# DDS_channel.net
KiCad netlist of a schematic drawn in Altium Designer
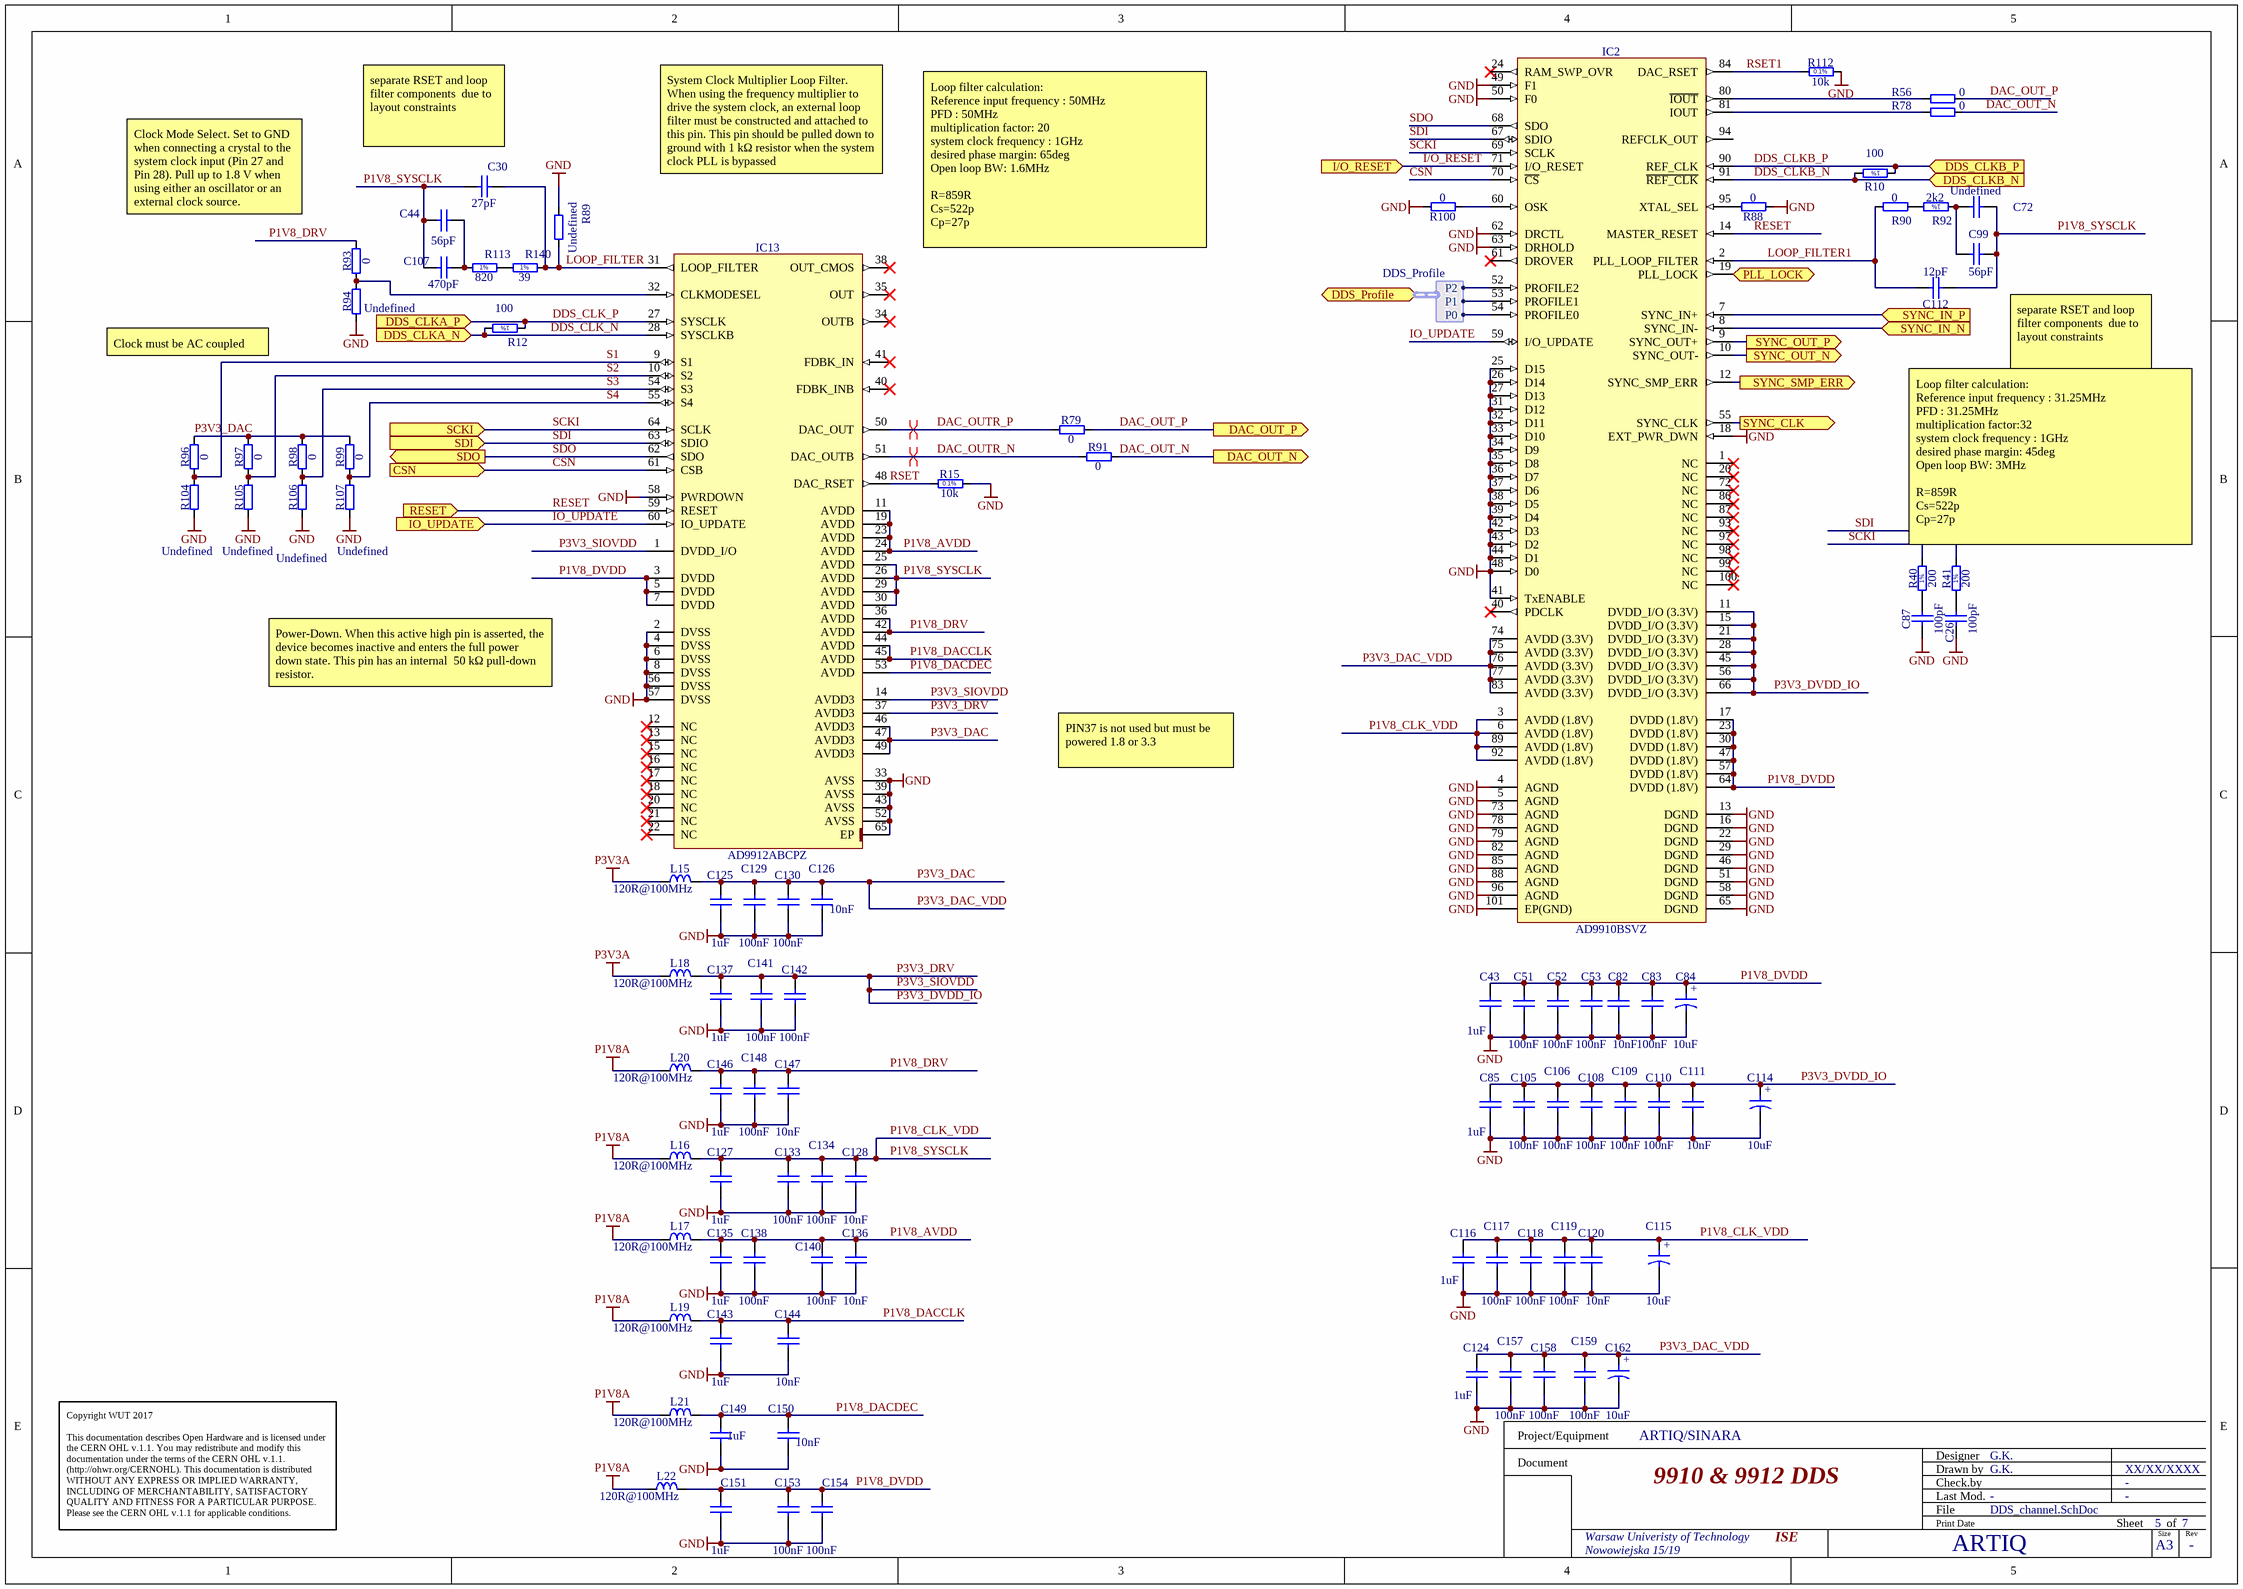
[diagram p0: DDS_channel.SchDoc]

(export (version "E")
  (design (tool "Eeschema 10.0.6"))
  (components
    (comp (ref "C26")
      (value "100pF")
      (footprint "CAPC1005X55N")
      (description "Non-polarised capacitor")
      (fields
        (field (name "PART NUMBER") "CC0402_100PF_50V_5%_C0G")
        (field (name "VOLTAGE") "50V")
        (field (name "AUTHOR") "CERN DEM JLC")
      )
      (libsource (lib "Capacitors") (part "Capacitor - non polarized"))
    )
    (comp (ref "C30")
      (value "27pF")
      (footprint "CAPC1608X87N")
      (description "Non-polarised capacitor")
      (fields
        (field (name "PART NUMBER") "CC0603_27PF_50V_5%_NP0")
        (field (name "VOLTAGE") "50V")
        (field (name "AUTHOR") "CERN DEM JLC")
      )
      (libsource (lib "Capacitors") (part "Capacitor - non polarized"))
    )
    (comp (ref "C43")
      (value "1uF")
      (footprint "CAPC1005X55N")
      (description "Non-polarised capacitor")
      (fields
        (field (name "PART NUMBER") "CC0402_1UF_16V_10%_X5R")
        (field (name "VOLTAGE") "16V")
        (field (name "AUTHOR") "CERN DEM JLC")
      )
      (libsource (lib "Capacitors") (part "Capacitor - non polarized"))
    )
    (comp (ref "C44")
      (value "56pF")
      (footprint "CAPC1608X87N")
      (description "Non-polarised capacitor")
      (fields
        (field (name "PART NUMBER") "CC0603_56PF_50V_5%_NP0")
        (field (name "VOLTAGE") "50V")
        (field (name "AUTHOR") "CERN DEM JLC")
      )
      (libsource (lib "Capacitors") (part "Capacitor - non polarized"))
    )
    (comp (ref "C51")
      (value "100nF")
      (footprint "CAPC1005X55N")
      (description "Non-polarised capacitor")
      (fields
        (field (name "PART NUMBER") "CC0402_100NF_16V_10%_X5R")
        (field (name "VOLTAGE") "16V")
        (field (name "AUTHOR") "CERN DEM JLC")
      )
      (libsource (lib "Capacitors") (part "Capacitor - non polarized"))
    )
    (comp (ref "C52")
      (value "100nF")
      (footprint "CAPC1005X55N")
      (description "Non-polarised capacitor")
      (fields
        (field (name "PART NUMBER") "CC0402_100NF_16V_10%_X5R")
        (field (name "VOLTAGE") "16V")
        (field (name "AUTHOR") "CERN DEM JLC")
      )
      (libsource (lib "Capacitors") (part "Capacitor - non polarized"))
    )
    (comp (ref "C53")
      (value "100nF")
      (footprint "CAPC1005X55N")
      (description "Non-polarised capacitor")
      (fields
        (field (name "PART NUMBER") "CC0402_100NF_16V_10%_X5R")
        (field (name "VOLTAGE") "16V")
        (field (name "AUTHOR") "CERN DEM JLC")
      )
      (libsource (lib "Capacitors") (part "Capacitor - non polarized"))
    )
    (comp (ref "C72")
      (value "Undefined")
      (footprint "CAPC1608X90N")
      (description "Non-polarised capacitor")
      (fields (field (name "PART NUMBER") "CC0603_NO-VALUE") (field (name "AUTHOR") "CERN DEM MR"))
      (libsource (lib "Capacitors") (part "Capacitor - non polarized"))
    )
    (comp (ref "C82")
      (value "10nF")
      (footprint "CAPC1005X55N")
      (description "Non-polarised capacitor")
      (fields
        (field (name "PART NUMBER") "CC0402_10NF_16V_10%_X7R")
        (field (name "VOLTAGE") "16V")
        (field (name "AUTHOR") "CERN DEM JLC")
      )
      (libsource (lib "Capacitors") (part "Capacitor - non polarized"))
    )
    (comp (ref "C83")
      (value "100nF")
      (footprint "CAPC1005X55N")
      (description "Non-polarised capacitor")
      (fields
        (field (name "PART NUMBER") "CC0402_100NF_16V_10%_X5R")
        (field (name "VOLTAGE") "16V")
        (field (name "AUTHOR") "CERN DEM JLC")
      )
      (libsource (lib "Capacitors") (part "Capacitor - non polarized"))
    )
    (comp (ref "C84")
      (value "10uF")
      (footprint "CAPMP6032X280N")
      (description "Polarised capacitor")
      (fields
        (field (name "PART NUMBER") "CTE6032-28_10UF_25V_10%_LESR0500")
        (field (name "VOLTAGE") "25V")
        (field (name "AUTHOR") "CERN DEM JLC")
      )
      (libsource (lib "Capacitors") (part "Capacitor - polarized"))
    )
    (comp (ref "C85")
      (value "1uF")
      (footprint "CAPC1005X55N")
      (description "Non-polarised capacitor")
      (fields
        (field (name "PART NUMBER") "CC0402_1UF_16V_10%_X5R")
        (field (name "VOLTAGE") "16V")
        (field (name "AUTHOR") "CERN DEM JLC")
      )
      (libsource (lib "Capacitors") (part "Capacitor - non polarized"))
    )
    (comp (ref "C87")
      (value "100pF")
      (footprint "CAPC1005X55N")
      (description "Non-polarised capacitor")
      (fields
        (field (name "PART NUMBER") "CC0402_100PF_50V_5%_C0G")
        (field (name "VOLTAGE") "50V")
        (field (name "AUTHOR") "CERN DEM JLC")
      )
      (libsource (lib "Capacitors") (part "Capacitor - non polarized"))
    )
    (comp (ref "C99")
      (value "56pF")
      (footprint "CAPC1608X87N")
      (description "Non-polarised capacitor")
      (fields
        (field (name "PART NUMBER") "CC0603_56PF_50V_5%_NP0")
        (field (name "VOLTAGE") "50V")
        (field (name "AUTHOR") "CERN DEM JLC")
      )
      (libsource (lib "Capacitors") (part "Capacitor - non polarized"))
    )
    (comp (ref "C105")
      (value "100nF")
      (footprint "CAPC1005X55N")
      (description "Non-polarised capacitor")
      (fields
        (field (name "PART NUMBER") "CC0402_100NF_16V_10%_X5R")
        (field (name "VOLTAGE") "16V")
        (field (name "AUTHOR") "CERN DEM JLC")
      )
      (libsource (lib "Capacitors") (part "Capacitor - non polarized"))
    )
    (comp (ref "C106")
      (value "100nF")
      (footprint "CAPC1005X55N")
      (description "Non-polarised capacitor")
      (fields
        (field (name "PART NUMBER") "CC0402_100NF_16V_10%_X5R")
        (field (name "VOLTAGE") "16V")
        (field (name "AUTHOR") "CERN DEM JLC")
      )
      (libsource (lib "Capacitors") (part "Capacitor - non polarized"))
    )
    (comp (ref "C107")
      (value "470pF")
      (footprint "CAPC1608X87N")
      (description "Non-polarised capacitor")
      (fields
        (field (name "PART NUMBER") "CC0603_470PF_50V_5%_NP0")
        (field (name "VOLTAGE") "50V")
        (field (name "AUTHOR") "CERN DEM JLC")
      )
      (libsource (lib "Capacitors") (part "Capacitor - non polarized"))
    )
    (comp (ref "C108")
      (value "100nF")
      (footprint "CAPC1005X55N")
      (description "Non-polarised capacitor")
      (fields
        (field (name "PART NUMBER") "CC0402_100NF_16V_10%_X5R")
        (field (name "VOLTAGE") "16V")
        (field (name "AUTHOR") "CERN DEM JLC")
      )
      (libsource (lib "Capacitors") (part "Capacitor - non polarized"))
    )
    (comp (ref "C109")
      (value "100nF")
      (footprint "CAPC1005X55N")
      (description "Non-polarised capacitor")
      (fields
        (field (name "PART NUMBER") "CC0402_100NF_16V_10%_X5R")
        (field (name "VOLTAGE") "16V")
        (field (name "AUTHOR") "CERN DEM JLC")
      )
      (libsource (lib "Capacitors") (part "Capacitor - non polarized"))
    )
    (comp (ref "C110")
      (value "100nF")
      (footprint "CAPC1005X55N")
      (description "Non-polarised capacitor")
      (fields
        (field (name "PART NUMBER") "CC0402_100NF_16V_10%_X5R")
        (field (name "VOLTAGE") "16V")
        (field (name "AUTHOR") "CERN DEM JLC")
      )
      (libsource (lib "Capacitors") (part "Capacitor - non polarized"))
    )
    (comp (ref "C111")
      (value "10nF")
      (footprint "CAPC1005X55N")
      (description "Non-polarised capacitor")
      (fields
        (field (name "PART NUMBER") "CC0402_10NF_16V_10%_X7R")
        (field (name "VOLTAGE") "16V")
        (field (name "AUTHOR") "CERN DEM JLC")
      )
      (libsource (lib "Capacitors") (part "Capacitor - non polarized"))
    )
    (comp (ref "C112")
      (value "12pF")
      (footprint "CAPC1608X87N")
      (description "Non-polarised capacitor")
      (fields
        (field (name "PART NUMBER") "CC0603_12PF_50V_5%_NP0")
        (field (name "VOLTAGE") "50V")
        (field (name "AUTHOR") "CERN DEM JLC")
      )
      (libsource (lib "Capacitors") (part "Capacitor - non polarized"))
    )
    (comp (ref "C114")
      (value "10uF")
      (footprint "CAPMP6032X280N")
      (description "Polarised capacitor")
      (fields
        (field (name "PART NUMBER") "CTE6032-28_10UF_25V_10%_LESR0500")
        (field (name "VOLTAGE") "25V")
        (field (name "AUTHOR") "CERN DEM JLC")
      )
      (libsource (lib "Capacitors") (part "Capacitor - polarized"))
    )
    (comp (ref "C115")
      (value "10uF")
      (footprint "CAPMP6032X280N")
      (description "Polarised capacitor")
      (fields
        (field (name "PART NUMBER") "CTE6032-28_10UF_25V_10%_LESR0500")
        (field (name "VOLTAGE") "25V")
        (field (name "AUTHOR") "CERN DEM JLC")
      )
      (libsource (lib "Capacitors") (part "Capacitor - polarized"))
    )
    (comp (ref "C116")
      (value "1uF")
      (footprint "CAPC1005X55N")
      (description "Non-polarised capacitor")
      (fields
        (field (name "PART NUMBER") "CC0402_1UF_16V_10%_X5R")
        (field (name "VOLTAGE") "16V")
        (field (name "AUTHOR") "CERN DEM JLC")
      )
      (libsource (lib "Capacitors") (part "Capacitor - non polarized"))
    )
    (comp (ref "C117")
      (value "100nF")
      (footprint "CAPC1005X55N")
      (description "Non-polarised capacitor")
      (fields
        (field (name "PART NUMBER") "CC0402_100NF_16V_10%_X5R")
        (field (name "VOLTAGE") "16V")
        (field (name "AUTHOR") "CERN DEM JLC")
      )
      (libsource (lib "Capacitors") (part "Capacitor - non polarized"))
    )
    (comp (ref "C118")
      (value "100nF")
      (footprint "CAPC1005X55N")
      (description "Non-polarised capacitor")
      (fields
        (field (name "PART NUMBER") "CC0402_100NF_16V_10%_X5R")
        (field (name "VOLTAGE") "16V")
        (field (name "AUTHOR") "CERN DEM JLC")
      )
      (libsource (lib "Capacitors") (part "Capacitor - non polarized"))
    )
    (comp (ref "C119")
      (value "100nF")
      (footprint "CAPC1005X55N")
      (description "Non-polarised capacitor")
      (fields
        (field (name "PART NUMBER") "CC0402_100NF_16V_10%_X5R")
        (field (name "VOLTAGE") "16V")
        (field (name "AUTHOR") "CERN DEM JLC")
      )
      (libsource (lib "Capacitors") (part "Capacitor - non polarized"))
    )
    (comp (ref "C120")
      (value "10nF")
      (footprint "CAPC1005X55N")
      (description "Non-polarised capacitor")
      (fields
        (field (name "PART NUMBER") "CC0402_10NF_16V_10%_X7R")
        (field (name "VOLTAGE") "16V")
        (field (name "AUTHOR") "CERN DEM JLC")
      )
      (libsource (lib "Capacitors") (part "Capacitor - non polarized"))
    )
    (comp (ref "C124")
      (value "1uF")
      (footprint "CAPC1005X55N")
      (description "Non-polarised capacitor")
      (fields
        (field (name "PART NUMBER") "CC0402_1UF_16V_10%_X5R")
        (field (name "VOLTAGE") "16V")
        (field (name "AUTHOR") "CERN DEM JLC")
      )
      (libsource (lib "Capacitors") (part "Capacitor - non polarized"))
    )
    (comp (ref "C125")
      (value "1uF")
      (footprint "CAPC1005X55N")
      (description "Non-polarised capacitor")
      (fields
        (field (name "PART NUMBER") "CC0402_1UF_16V_10%_X5R")
        (field (name "VOLTAGE") "16V")
        (field (name "AUTHOR") "CERN DEM JLC")
      )
      (libsource (lib "Capacitors") (part "Capacitor - non polarized"))
    )
    (comp (ref "C126")
      (value "10nF")
      (footprint "CAPC1005X55N")
      (description "Non-polarised capacitor")
      (fields
        (field (name "PART NUMBER") "CC0402_10NF_16V_10%_X7R")
        (field (name "VOLTAGE") "16V")
        (field (name "AUTHOR") "CERN DEM JLC")
      )
      (libsource (lib "Capacitors") (part "Capacitor - non polarized"))
    )
    (comp (ref "C127")
      (value "1uF")
      (footprint "CAPC1005X55N")
      (description "Non-polarised capacitor")
      (fields
        (field (name "PART NUMBER") "CC0402_1UF_16V_10%_X5R")
        (field (name "VOLTAGE") "16V")
        (field (name "AUTHOR") "CERN DEM JLC")
      )
      (libsource (lib "Capacitors") (part "Capacitor - non polarized"))
    )
    (comp (ref "C128")
      (value "10nF")
      (footprint "CAPC1005X55N")
      (description "Non-polarised capacitor")
      (fields
        (field (name "PART NUMBER") "CC0402_10NF_16V_10%_X7R")
        (field (name "VOLTAGE") "16V")
        (field (name "AUTHOR") "CERN DEM JLC")
      )
      (libsource (lib "Capacitors") (part "Capacitor - non polarized"))
    )
    (comp (ref "C129")
      (value "100nF")
      (footprint "CAPC1005X55N")
      (description "Non-polarised capacitor")
      (fields
        (field (name "PART NUMBER") "CC0402_100NF_16V_10%_X5R")
        (field (name "VOLTAGE") "16V")
        (field (name "AUTHOR") "CERN DEM JLC")
      )
      (libsource (lib "Capacitors") (part "Capacitor - non polarized"))
    )
    (comp (ref "C130")
      (value "100nF")
      (footprint "CAPC1005X55N")
      (description "Non-polarised capacitor")
      (fields
        (field (name "PART NUMBER") "CC0402_100NF_16V_10%_X5R")
        (field (name "VOLTAGE") "16V")
        (field (name "AUTHOR") "CERN DEM JLC")
      )
      (libsource (lib "Capacitors") (part "Capacitor - non polarized"))
    )
    (comp (ref "C133")
      (value "100nF")
      (footprint "CAPC1005X55N")
      (description "Non-polarised capacitor")
      (fields
        (field (name "PART NUMBER") "CC0402_100NF_16V_10%_X5R")
        (field (name "VOLTAGE") "16V")
        (field (name "AUTHOR") "CERN DEM JLC")
      )
      (libsource (lib "Capacitors") (part "Capacitor - non polarized"))
    )
    (comp (ref "C134")
      (value "100nF")
      (footprint "CAPC1005X55N")
      (description "Non-polarised capacitor")
      (fields
        (field (name "PART NUMBER") "CC0402_100NF_16V_10%_X5R")
        (field (name "VOLTAGE") "16V")
        (field (name "AUTHOR") "CERN DEM JLC")
      )
      (libsource (lib "Capacitors") (part "Capacitor - non polarized"))
    )
    (comp (ref "C135")
      (value "1uF")
      (footprint "CAPC1005X55N")
      (description "Non-polarised capacitor")
      (fields
        (field (name "PART NUMBER") "CC0402_1UF_16V_10%_X5R")
        (field (name "VOLTAGE") "16V")
        (field (name "AUTHOR") "CERN DEM JLC")
      )
      (libsource (lib "Capacitors") (part "Capacitor - non polarized"))
    )
    (comp (ref "C136")
      (value "10nF")
      (footprint "CAPC1005X55N")
      (description "Non-polarised capacitor")
      (fields
        (field (name "PART NUMBER") "CC0402_10NF_16V_10%_X7R")
        (field (name "VOLTAGE") "16V")
        (field (name "AUTHOR") "CERN DEM JLC")
      )
      (libsource (lib "Capacitors") (part "Capacitor - non polarized"))
    )
    (comp (ref "C137")
      (value "1uF")
      (footprint "CAPC1005X55N")
      (description "Non-polarised capacitor")
      (fields
        (field (name "PART NUMBER") "CC0402_1UF_16V_10%_X5R")
        (field (name "VOLTAGE") "16V")
        (field (name "AUTHOR") "CERN DEM JLC")
      )
      (libsource (lib "Capacitors") (part "Capacitor - non polarized"))
    )
    (comp (ref "C138")
      (value "100nF")
      (footprint "CAPC1005X55N")
      (description "Non-polarised capacitor")
      (fields
        (field (name "PART NUMBER") "CC0402_100NF_16V_10%_X5R")
        (field (name "VOLTAGE") "16V")
        (field (name "AUTHOR") "CERN DEM JLC")
      )
      (libsource (lib "Capacitors") (part "Capacitor - non polarized"))
    )
    (comp (ref "C140")
      (value "100nF")
      (footprint "CAPC1005X55N")
      (description "Non-polarised capacitor")
      (fields
        (field (name "PART NUMBER") "CC0402_100NF_16V_10%_X5R")
        (field (name "VOLTAGE") "16V")
        (field (name "AUTHOR") "CERN DEM JLC")
      )
      (libsource (lib "Capacitors") (part "Capacitor - non polarized"))
    )
    (comp (ref "C141")
      (value "100nF")
      (footprint "CAPC1005X55N")
      (description "Non-polarised capacitor")
      (fields
        (field (name "PART NUMBER") "CC0402_100NF_16V_10%_X5R")
        (field (name "VOLTAGE") "16V")
        (field (name "AUTHOR") "CERN DEM JLC")
      )
      (libsource (lib "Capacitors") (part "Capacitor - non polarized"))
    )
    (comp (ref "C142")
      (value "100nF")
      (footprint "CAPC1005X55N")
      (description "Non-polarised capacitor")
      (fields
        (field (name "PART NUMBER") "CC0402_100NF_16V_10%_X5R")
        (field (name "VOLTAGE") "16V")
        (field (name "AUTHOR") "CERN DEM JLC")
      )
      (libsource (lib "Capacitors") (part "Capacitor - non polarized"))
    )
    (comp (ref "C143")
      (value "1uF")
      (footprint "CAPC1005X55N")
      (description "Non-polarised capacitor")
      (fields
        (field (name "PART NUMBER") "CC0402_1UF_16V_10%_X5R")
        (field (name "VOLTAGE") "16V")
        (field (name "AUTHOR") "CERN DEM JLC")
      )
      (libsource (lib "Capacitors") (part "Capacitor - non polarized"))
    )
    (comp (ref "C144")
      (value "10nF")
      (footprint "CAPC1005X55N")
      (description "Non-polarised capacitor")
      (fields
        (field (name "PART NUMBER") "CC0402_10NF_16V_10%_X7R")
        (field (name "VOLTAGE") "16V")
        (field (name "AUTHOR") "CERN DEM JLC")
      )
      (libsource (lib "Capacitors") (part "Capacitor - non polarized"))
    )
    (comp (ref "C146")
      (value "1uF")
      (footprint "CAPC1005X55N")
      (description "Non-polarised capacitor")
      (fields
        (field (name "PART NUMBER") "CC0402_1UF_16V_10%_X5R")
        (field (name "VOLTAGE") "16V")
        (field (name "AUTHOR") "CERN DEM JLC")
      )
      (libsource (lib "Capacitors") (part "Capacitor - non polarized"))
    )
    (comp (ref "C147")
      (value "10nF")
      (footprint "CAPC1005X55N")
      (description "Non-polarised capacitor")
      (fields
        (field (name "PART NUMBER") "CC0402_10NF_16V_10%_X7R")
        (field (name "VOLTAGE") "16V")
        (field (name "AUTHOR") "CERN DEM JLC")
      )
      (libsource (lib "Capacitors") (part "Capacitor - non polarized"))
    )
    (comp (ref "C148")
      (value "100nF")
      (footprint "CAPC1005X55N")
      (description "Non-polarised capacitor")
      (fields
        (field (name "PART NUMBER") "CC0402_100NF_16V_10%_X5R")
        (field (name "VOLTAGE") "16V")
        (field (name "AUTHOR") "CERN DEM JLC")
      )
      (libsource (lib "Capacitors") (part "Capacitor - non polarized"))
    )
    (comp (ref "C149")
      (value "1uF")
      (footprint "CAPC1005X55N")
      (description "Non-polarised capacitor")
      (fields
        (field (name "PART NUMBER") "CC0402_1UF_16V_10%_X5R")
        (field (name "VOLTAGE") "16V")
        (field (name "AUTHOR") "CERN DEM JLC")
      )
      (libsource (lib "Capacitors") (part "Capacitor - non polarized"))
    )
    (comp (ref "C150")
      (value "10nF")
      (footprint "CAPC1005X55N")
      (description "Non-polarised capacitor")
      (fields
        (field (name "PART NUMBER") "CC0402_10NF_16V_10%_X7R")
        (field (name "VOLTAGE") "16V")
        (field (name "AUTHOR") "CERN DEM JLC")
      )
      (libsource (lib "Capacitors") (part "Capacitor - non polarized"))
    )
    (comp (ref "C151")
      (value "1uF")
      (footprint "CAPC1005X55N")
      (description "Non-polarised capacitor")
      (fields
        (field (name "PART NUMBER") "CC0402_1UF_16V_10%_X5R")
        (field (name "VOLTAGE") "16V")
        (field (name "AUTHOR") "CERN DEM JLC")
      )
      (libsource (lib "Capacitors") (part "Capacitor - non polarized"))
    )
    (comp (ref "C153")
      (value "100nF")
      (footprint "CAPC1005X55N")
      (description "Non-polarised capacitor")
      (fields
        (field (name "PART NUMBER") "CC0402_100NF_16V_10%_X5R")
        (field (name "VOLTAGE") "16V")
        (field (name "AUTHOR") "CERN DEM JLC")
      )
      (libsource (lib "Capacitors") (part "Capacitor - non polarized"))
    )
    (comp (ref "C154")
      (value "100nF")
      (footprint "CAPC1005X55N")
      (description "Non-polarised capacitor")
      (fields
        (field (name "PART NUMBER") "CC0402_100NF_16V_10%_X5R")
        (field (name "VOLTAGE") "16V")
        (field (name "AUTHOR") "CERN DEM JLC")
      )
      (libsource (lib "Capacitors") (part "Capacitor - non polarized"))
    )
    (comp (ref "C157")
      (value "100nF")
      (footprint "CAPC1005X55N")
      (description "Non-polarised capacitor")
      (fields
        (field (name "PART NUMBER") "CC0402_100NF_16V_10%_X5R")
        (field (name "VOLTAGE") "16V")
        (field (name "AUTHOR") "CERN DEM JLC")
      )
      (libsource (lib "Capacitors") (part "Capacitor - non polarized"))
    )
    (comp (ref "C158")
      (value "100nF")
      (footprint "CAPC1005X55N")
      (description "Non-polarised capacitor")
      (fields
        (field (name "PART NUMBER") "CC0402_100NF_16V_10%_X5R")
        (field (name "VOLTAGE") "16V")
        (field (name "AUTHOR") "CERN DEM JLC")
      )
      (libsource (lib "Capacitors") (part "Capacitor - non polarized"))
    )
    (comp (ref "C159")
      (value "100nF")
      (footprint "CAPC1005X55N")
      (description "Non-polarised capacitor")
      (fields
        (field (name "PART NUMBER") "CC0402_100NF_16V_10%_X5R")
        (field (name "VOLTAGE") "16V")
        (field (name "AUTHOR") "CERN DEM JLC")
      )
      (libsource (lib "Capacitors") (part "Capacitor - non polarized"))
    )
    (comp (ref "C162")
      (value "10uF")
      (footprint "CAPMP6032X280N")
      (description "Polarised capacitor")
      (fields
        (field (name "PART NUMBER") "CTE6032-28_10UF_25V_10%_LESR0500")
        (field (name "VOLTAGE") "25V")
        (field (name "AUTHOR") "CERN DEM JLC")
      )
      (libsource (lib "Capacitors") (part "Capacitor - polarized"))
    )
    (comp (ref "IC2")
      (value "AD9910BSVZ")
      (footprint "QFP50P1600X1600X120-101N-S500")
      (description "1 GSPS, 14-Bit, 3.3 V CMOS Direct Digital Synthesizer")
      (fields (field (name "MANUFACTURER") "ANALOG DEVICES") (field (name "AUTHOR") "CERN DEM JLC"))
      (libsource (lib "ICs And Semiconductors") (part "AD9910"))
    )
    (comp (ref "IC13")
      (value "AD9912ABCPZ")
      (footprint "QFN50P900X900X100-65N-S536")
      (description "1 GSPS Direct Digital Synthetizer with 14-Bit DAC")
      (fields (field (name "MANUFACTURER") "ANALOG DEVICES") (field (name "AUTHOR") "CERN DEM JLC"))
      (libsource (lib "ICs And Semiconductors") (part "AD9912"))
    )
    (comp (ref "L15")
      (value "120R@100MHz")
      (footprint "INDC1608X95N")
      (description "Inductor")
      (fields
        (field (name "PART NUMBER") "IND0603_MURATA_BLM18PG121SN1D")
        (field (name "POWER") "2A")
        (field (name "AUTHOR") "CERN DEM BC")
      )
      (libsource (lib "Inductors & Transformers") (part "Inductor"))
    )
    (comp (ref "L16")
      (value "120R@100MHz")
      (footprint "INDC1608X95N")
      (description "Inductor")
      (fields
        (field (name "PART NUMBER") "IND0603_MURATA_BLM18PG121SN1D")
        (field (name "POWER") "2A")
        (field (name "AUTHOR") "CERN DEM BC")
      )
      (libsource (lib "Inductors & Transformers") (part "Inductor"))
    )
    (comp (ref "L17")
      (value "120R@100MHz")
      (footprint "INDC1608X95N")
      (description "Inductor")
      (fields
        (field (name "PART NUMBER") "IND0603_MURATA_BLM18PG121SN1D")
        (field (name "POWER") "2A")
        (field (name "AUTHOR") "CERN DEM BC")
      )
      (libsource (lib "Inductors & Transformers") (part "Inductor"))
    )
    (comp (ref "L18")
      (value "120R@100MHz")
      (footprint "INDC1608X95N")
      (description "Inductor")
      (fields
        (field (name "PART NUMBER") "IND0603_MURATA_BLM18PG121SN1D")
        (field (name "POWER") "2A")
        (field (name "AUTHOR") "CERN DEM BC")
      )
      (libsource (lib "Inductors & Transformers") (part "Inductor"))
    )
    (comp (ref "L19")
      (value "120R@100MHz")
      (footprint "INDC1608X95N")
      (description "Inductor")
      (fields
        (field (name "PART NUMBER") "IND0603_MURATA_BLM18PG121SN1D")
        (field (name "POWER") "2A")
        (field (name "AUTHOR") "CERN DEM BC")
      )
      (libsource (lib "Inductors & Transformers") (part "Inductor"))
    )
    (comp (ref "L20")
      (value "120R@100MHz")
      (footprint "INDC1608X95N")
      (description "Inductor")
      (fields
        (field (name "PART NUMBER") "IND0603_MURATA_BLM18PG121SN1D")
        (field (name "POWER") "2A")
        (field (name "AUTHOR") "CERN DEM BC")
      )
      (libsource (lib "Inductors & Transformers") (part "Inductor"))
    )
    (comp (ref "L21")
      (value "120R@100MHz")
      (footprint "INDC1608X95N")
      (description "Inductor")
      (fields
        (field (name "PART NUMBER") "IND0603_MURATA_BLM18PG121SN1D")
        (field (name "POWER") "2A")
        (field (name "AUTHOR") "CERN DEM BC")
      )
      (libsource (lib "Inductors & Transformers") (part "Inductor"))
    )
    (comp (ref "L22")
      (value "120R@100MHz")
      (footprint "INDC1608X95N")
      (description "Inductor")
      (fields
        (field (name "PART NUMBER") "IND0603_MURATA_BLM18PG121SN1D")
        (field (name "POWER") "2A")
        (field (name "AUTHOR") "CERN DEM BC")
      )
      (libsource (lib "Inductors & Transformers") (part "Inductor"))
    )
    (comp (ref "R10")
      (value "100")
      (footprint "RESC1005X40N")
      (description "Resistor - 1%")
      (fields
        (field (name "PART NUMBER") "R0402_100R_1%_0.0625W_100PPM")
        (field (name "POWER") "0.0625W")
        (field (name "AUTHOR") "CERN DEM JLC")
      )
      (libsource (lib "Resistors") (part "Resistor - 1%"))
    )
    (comp (ref "R12")
      (value "100")
      (footprint "RESC1005X40N")
      (description "Resistor - 1%")
      (fields
        (field (name "PART NUMBER") "R0402_100R_1%_0.0625W_100PPM")
        (field (name "POWER") "0.0625W")
        (field (name "AUTHOR") "CERN DEM JLC")
      )
      (libsource (lib "Resistors") (part "Resistor - 1%"))
    )
    (comp (ref "R15")
      (value "10k")
      (footprint "RESC1005X35N")
      (description "Resistor - 0.1%")
      (fields
        (field (name "PART NUMBER") "R0402_10K_0.1%_0.063W_25PPM")
        (field (name "POWER") "0.063W")
        (field (name "AUTHOR") "CERN DEM JMW")
      )
      (libsource (lib "Resistors") (part "Resistor - 0.1%"))
    )
    (comp (ref "R40")
      (value "200")
      (footprint "RESC1005X40N")
      (description "Resistor - 1%")
      (fields
        (field (name "PART NUMBER") "R0402_200R_1%_0.0625W_100PPM")
        (field (name "POWER") "0.0625W")
        (field (name "AUTHOR") "CERN DEM JLC")
      )
      (libsource (lib "Resistors") (part "Resistor - 1%"))
    )
    (comp (ref "R41")
      (value "200")
      (footprint "RESC1005X40N")
      (description "Resistor - 1%")
      (fields
        (field (name "PART NUMBER") "R0402_200R_1%_0.0625W_100PPM")
        (field (name "POWER") "0.0625W")
        (field (name "AUTHOR") "CERN DEM JLC")
      )
      (libsource (lib "Resistors") (part "Resistor - 1%"))
    )
    (comp (ref "R56")
      (value "0")
      (footprint "RESC1005X40N")
      (description "Resistor")
      (fields
        (field (name "PART NUMBER") "R0402_0R_JUMPER")
        (field (name "MANUFACTURER") "GENERIC")
        (field (name "AUTHOR") "CERN DEM JLC")
      )
      (libsource (lib "Resistors") (part "Resistor"))
    )
    (comp (ref "R78")
      (value "0")
      (footprint "RESC1005X40N")
      (description "Resistor")
      (fields
        (field (name "PART NUMBER") "R0402_0R_JUMPER")
        (field (name "MANUFACTURER") "GENERIC")
        (field (name "AUTHOR") "CERN DEM JLC")
      )
      (libsource (lib "Resistors") (part "Resistor"))
    )
    (comp (ref "R79")
      (value "0")
      (footprint "RESC1005X40N")
      (description "Resistor")
      (fields
        (field (name "PART NUMBER") "R0402_0R_JUMPER")
        (field (name "MANUFACTURER") "GENERIC")
        (field (name "AUTHOR") "CERN DEM JLC")
      )
      (libsource (lib "Resistors") (part "Resistor"))
    )
    (comp (ref "R88")
      (value "0")
      (footprint "RESC1005X40N")
      (description "Resistor")
      (fields
        (field (name "PART NUMBER") "R0402_0R_JUMPER")
        (field (name "MANUFACTURER") "GENERIC")
        (field (name "AUTHOR") "CERN DEM JLC")
      )
      (libsource (lib "Resistors") (part "Resistor"))
    )
    (comp (ref "R89")
      (value "Undefined")
      (footprint "RESC1005X40N")
      (description "Resistor")
      (fields (field (name "PART NUMBER") "R0402_NO-VALUE") (field (name "AUTHOR") "CERN DEM JLC"))
      (libsource (lib "Resistors") (part "Resistor"))
    )
    (comp (ref "R90")
      (value "0")
      (footprint "RESC1608X55N")
      (description "Resistor")
      (fields
        (field (name "PART NUMBER") "R0603_0R_JUMPER")
        (field (name "MANUFACTURER") "GENERIC")
        (field (name "AUTHOR") "CERN DEM JLC")
      )
      (libsource (lib "Resistors") (part "Resistor"))
    )
    (comp (ref "R91")
      (value "0")
      (footprint "RESC1005X40N")
      (description "Resistor")
      (fields
        (field (name "PART NUMBER") "R0402_0R_JUMPER")
        (field (name "MANUFACTURER") "GENERIC")
        (field (name "AUTHOR") "CERN DEM JLC")
      )
      (libsource (lib "Resistors") (part "Resistor"))
    )
    (comp (ref "R92")
      (value "2k2")
      (footprint "RESC1608X55N")
      (description "Resistor - 1%")
      (fields
        (field (name "PART NUMBER") "R0603_2K2_1%_0.1W_100PPM")
        (field (name "POWER") "0.1W")
        (field (name "AUTHOR") "CERN DEM JLC")
      )
      (libsource (lib "Resistors") (part "Resistor - 1%"))
    )
    (comp (ref "R93")
      (value "0")
      (footprint "RESC1005X40N")
      (description "Resistor")
      (fields
        (field (name "PART NUMBER") "R0402_0R_JUMPER")
        (field (name "MANUFACTURER") "GENERIC")
        (field (name "AUTHOR") "CERN DEM JLC")
      )
      (libsource (lib "Resistors") (part "Resistor"))
    )
    (comp (ref "R94")
      (value "Undefined")
      (footprint "RESC1005X40N")
      (description "Resistor")
      (fields (field (name "PART NUMBER") "R0402_NO-VALUE") (field (name "AUTHOR") "CERN DEM JLC"))
      (libsource (lib "Resistors") (part "Resistor"))
    )
    (comp (ref "R96")
      (value "0")
      (footprint "RESC1005X40N")
      (description "Resistor")
      (fields
        (field (name "PART NUMBER") "R0402_0R_JUMPER")
        (field (name "MANUFACTURER") "GENERIC")
        (field (name "AUTHOR") "CERN DEM JLC")
      )
      (libsource (lib "Resistors") (part "Resistor"))
    )
    (comp (ref "R97")
      (value "0")
      (footprint "RESC1005X40N")
      (description "Resistor")
      (fields
        (field (name "PART NUMBER") "R0402_0R_JUMPER")
        (field (name "MANUFACTURER") "GENERIC")
        (field (name "AUTHOR") "CERN DEM JLC")
      )
      (libsource (lib "Resistors") (part "Resistor"))
    )
    (comp (ref "R98")
      (value "0")
      (footprint "RESC1005X40N")
      (description "Resistor")
      (fields
        (field (name "PART NUMBER") "R0402_0R_JUMPER")
        (field (name "MANUFACTURER") "GENERIC")
        (field (name "AUTHOR") "CERN DEM JLC")
      )
      (libsource (lib "Resistors") (part "Resistor"))
    )
    (comp (ref "R99")
      (value "0")
      (footprint "RESC1005X40N")
      (description "Resistor")
      (fields
        (field (name "PART NUMBER") "R0402_0R_JUMPER")
        (field (name "MANUFACTURER") "GENERIC")
        (field (name "AUTHOR") "CERN DEM JLC")
      )
      (libsource (lib "Resistors") (part "Resistor"))
    )
    (comp (ref "R100")
      (value "0")
      (footprint "RESC1005X40N")
      (description "Resistor")
      (fields
        (field (name "PART NUMBER") "R0402_0R_JUMPER")
        (field (name "MANUFACTURER") "GENERIC")
        (field (name "AUTHOR") "CERN DEM JLC")
      )
      (libsource (lib "Resistors") (part "Resistor"))
    )
    (comp (ref "R104")
      (value "Undefined")
      (footprint "RESC1005X40N")
      (description "Resistor")
      (fields (field (name "PART NUMBER") "R0402_NO-VALUE") (field (name "AUTHOR") "CERN DEM JLC"))
      (libsource (lib "Resistors") (part "Resistor"))
    )
    (comp (ref "R105")
      (value "Undefined")
      (footprint "RESC1005X40N")
      (description "Resistor")
      (fields (field (name "PART NUMBER") "R0402_NO-VALUE") (field (name "AUTHOR") "CERN DEM JLC"))
      (libsource (lib "Resistors") (part "Resistor"))
    )
    (comp (ref "R106")
      (value "Undefined")
      (footprint "RESC1005X40N")
      (description "Resistor")
      (fields (field (name "PART NUMBER") "R0402_NO-VALUE") (field (name "AUTHOR") "CERN DEM JLC"))
      (libsource (lib "Resistors") (part "Resistor"))
    )
    (comp (ref "R107")
      (value "Undefined")
      (footprint "RESC1005X40N")
      (description "Resistor")
      (fields (field (name "PART NUMBER") "R0402_NO-VALUE") (field (name "AUTHOR") "CERN DEM JLC"))
      (libsource (lib "Resistors") (part "Resistor"))
    )
    (comp (ref "R112")
      (value "10k")
      (footprint "RESC1005X35N")
      (description "Resistor - 0.1%")
      (fields
        (field (name "PART NUMBER") "R0402_10K_0.1%_0.063W_25PPM")
        (field (name "POWER") "0.063W")
        (field (name "AUTHOR") "CERN DEM JMW")
      )
      (libsource (lib "Resistors") (part "Resistor - 0.1%"))
    )
    (comp (ref "R113")
      (value "820")
      (footprint "RESC1608X55N")
      (description "Resistor - 1%")
      (fields
        (field (name "PART NUMBER") "R0603_820R_1%_0.1W_100PPM")
        (field (name "POWER") "0.1W")
        (field (name "AUTHOR") "CERN DEM JLC")
      )
      (libsource (lib "Resistors") (part "Resistor - 1%"))
    )
    (comp (ref "R140")
      (value "39")
      (footprint "RESC1608X55N")
      (description "Resistor - 1%")
      (fields
        (field (name "PART NUMBER") "R0603_39R_1%_0.1W_100PPM")
        (field (name "POWER") "0.1W")
        (field (name "AUTHOR") "CERN DEM JLC")
      )
      (libsource (lib "Resistors") (part "Resistor - 1%"))
    )
  )
  (nets
    (net (code "2") (name "/CSN") (class "Default")
      (node (ref "IC13") (pin "61") (pinfunction "CSB_61") (pintype "input"))
      (node (ref "IC2") (pin "70") (pinfunction "CS_70") (pintype "input"))
    )
    (net (code "3") (name "/DAC_OUTR_N") (class "Default")
      (node (ref "IC13") (pin "51") (pinfunction "DAC_OUTB_51") (pintype "output"))
      (node (ref "R91") (pin "1") (pinfunction "1_1") (pintype "passive"))
    )
    (net (code "4") (name "/DAC_OUTR_P") (class "Default")
      (node (ref "IC13") (pin "50") (pinfunction "DAC_OUT_50") (pintype "output"))
      (node (ref "R79") (pin "1") (pinfunction "1_1") (pintype "passive"))
    )
    (net (code "5") (name "/DAC_OUT_N") (class "Default")
      (node (ref "R78") (pin "2") (pinfunction "2_2") (pintype "passive"))
      (node (ref "R91") (pin "2") (pinfunction "2_2") (pintype "passive"))
    )
    (net (code "6") (name "/DAC_OUT_P") (class "Default")
      (node (ref "R56") (pin "2") (pinfunction "2_2") (pintype "passive"))
      (node (ref "R79") (pin "2") (pinfunction "2_2") (pintype "passive"))
    )
    (net (code "7") (name "/DDS_CLKB_N") (class "Default")
      (node (ref "IC2") (pin "91") (pinfunction "REF_CLK_91") (pintype "input"))
      (node (ref "R10") (pin "2") (pinfunction "2_2") (pintype "passive"))
    )
    (net (code "8") (name "/DDS_CLKB_P") (class "Default")
      (node (ref "IC2") (pin "90") (pinfunction "REF_CLK_90") (pintype "input"))
      (node (ref "R10") (pin "1") (pinfunction "1_1") (pintype "passive"))
    )
    (net (code "9") (name "/DDS_CLK_N") (class "Default")
      (node (ref "IC13") (pin "28") (pinfunction "SYSCLKB_28") (pintype "input"))
      (node (ref "R12") (pin "2") (pinfunction "2_2") (pintype "passive"))
    )
    (net (code "10") (name "/DDS_CLK_P") (class "Default")
      (node (ref "IC13") (pin "27") (pinfunction "SYSCLK_27") (pintype "input"))
      (node (ref "R12") (pin "1") (pinfunction "1_1") (pintype "passive"))
    )
    (net (code "11") (name "/IO_UPDATE") (class "Default")
      (node (ref "IC13") (pin "60") (pinfunction "IO_UPDATE_60") (pintype "input"))
      (node (ref "IC2") (pin "59") (pinfunction "I/O_UPDATE_59") (pintype "bidirectional"))
    )
    (net (code "12") (name "/I{slash}O_RESET") (class "Default")
      (node (ref "IC2") (pin "71") (pinfunction "I/O_RESET_71") (pintype "input"))
    )
    (net (code "13") (name "/LOOP_FILTER") (class "Default")
      (node (ref "C30") (pin "2") (pinfunction "2_2") (pintype "passive"))
      (node (ref "IC13") (pin "31") (pinfunction "LOOP_FILTER_31") (pintype "output"))
      (node (ref "R140") (pin "2") (pinfunction "2_2") (pintype "passive"))
      (node (ref "R89") (pin "1") (pinfunction "1_1") (pintype "passive"))
    )
    (net (code "14") (name "/LOOP_FILTER1") (class "Default")
      (node (ref "C112") (pin "2") (pinfunction "2_2") (pintype "passive"))
      (node (ref "IC2") (pin "2") (pinfunction "PLL_LOOP_FILTER_2") (pintype "input"))
      (node (ref "R90") (pin "2") (pinfunction "2_2") (pintype "passive"))
    )
    (net (code "15") (name "/P0") (class "Default")
      (node (ref "IC2") (pin "54") (pinfunction "PROFILE0_54") (pintype "input"))
    )
    (net (code "16") (name "/P1") (class "Default")
      (node (ref "IC2") (pin "53") (pinfunction "PROFILE1_53") (pintype "input"))
    )
    (net (code "17") (name "/P1V8_AVDD") (class "Default")
      (node (ref "C135") (pin "2") (pinfunction "2_2") (pintype "passive"))
      (node (ref "C136") (pin "2") (pinfunction "2_2") (pintype "passive"))
      (node (ref "C138") (pin "2") (pinfunction "2_2") (pintype "passive"))
      (node (ref "C140") (pin "2") (pinfunction "2_2") (pintype "passive"))
      (node (ref "IC13") (pin "11") (pinfunction "AVDD_11") (pintype "power_in"))
      (node (ref "IC13") (pin "19") (pinfunction "AVDD_19") (pintype "power_in"))
      (node (ref "IC13") (pin "23") (pinfunction "AVDD_23") (pintype "power_in"))
      (node (ref "IC13") (pin "24") (pinfunction "AVDD_24") (pintype "power_in"))
      (node (ref "L17") (pin "1") (pinfunction "1_1") (pintype "passive"))
    )
    (net (code "18") (name "/P1V8_CLK_VDD") (class "Default")
      (node (ref "C107") (pin "1") (pinfunction "1_1") (pintype "passive"))
      (node (ref "C112") (pin "1") (pinfunction "1_1") (pintype "passive"))
      (node (ref "C115") (pin "1") (pinfunction "1_1") (pintype "passive"))
      (node (ref "C116") (pin "2") (pinfunction "2_2") (pintype "passive"))
      (node (ref "C117") (pin "2") (pinfunction "2_2") (pintype "passive"))
      (node (ref "C118") (pin "2") (pinfunction "2_2") (pintype "passive"))
      (node (ref "C119") (pin "2") (pinfunction "2_2") (pintype "passive"))
      (node (ref "C120") (pin "2") (pinfunction "2_2") (pintype "passive"))
      (node (ref "C127") (pin "2") (pinfunction "2_2") (pintype "passive"))
      (node (ref "C128") (pin "2") (pinfunction "2_2") (pintype "passive"))
      (node (ref "C133") (pin "2") (pinfunction "2_2") (pintype "passive"))
      (node (ref "C134") (pin "2") (pinfunction "2_2") (pintype "passive"))
      (node (ref "C30") (pin "1") (pinfunction "1_1") (pintype "passive"))
      (node (ref "C44") (pin "1") (pinfunction "1_1") (pintype "passive"))
      (node (ref "C72") (pin "1") (pinfunction "1_1") (pintype "passive"))
      (node (ref "C99") (pin "1") (pinfunction "1_1") (pintype "passive"))
      (node (ref "IC13") (pin "25") (pinfunction "AVDD_25") (pintype "power_in"))
      (node (ref "IC13") (pin "26") (pinfunction "AVDD_26") (pintype "power_in"))
      (node (ref "IC13") (pin "29") (pinfunction "AVDD_29") (pintype "power_in"))
      (node (ref "IC13") (pin "30") (pinfunction "AVDD_30") (pintype "power_in"))
      (node (ref "IC2") (pin "3") (pinfunction "AVDD_(1.8V)_3") (pintype "power_in"))
      (node (ref "IC2") (pin "6") (pinfunction "AVDD_(1.8V)_6") (pintype "power_in"))
      (node (ref "IC2") (pin "89") (pinfunction "AVDD_(1.8V)_89") (pintype "power_in"))
      (node (ref "IC2") (pin "92") (pinfunction "AVDD_(1.8V)_92") (pintype "power_in"))
      (node (ref "L16") (pin "1") (pinfunction "1_1") (pintype "passive"))
    )
    (net (code "19") (name "/P1V8_DACCLK") (class "Default")
      (node (ref "C143") (pin "2") (pinfunction "2_2") (pintype "passive"))
      (node (ref "C144") (pin "2") (pinfunction "2_2") (pintype "passive"))
      (node (ref "IC13") (pin "44") (pinfunction "AVDD_44") (pintype "power_in"))
      (node (ref "IC13") (pin "45") (pinfunction "AVDD_45") (pintype "power_in"))
      (node (ref "L19") (pin "1") (pinfunction "1_1") (pintype "passive"))
    )
    (net (code "20") (name "/P1V8_DACDEC") (class "Default")
      (node (ref "C149") (pin "2") (pinfunction "2_2") (pintype "passive"))
      (node (ref "C150") (pin "2") (pinfunction "2_2") (pintype "passive"))
      (node (ref "IC13") (pin "53") (pinfunction "AVDD_53") (pintype "power_in"))
      (node (ref "L21") (pin "1") (pinfunction "1_1") (pintype "passive"))
    )
    (net (code "21") (name "/P1V8_DRV") (class "Default")
      (node (ref "C146") (pin "2") (pinfunction "2_2") (pintype "passive"))
      (node (ref "C147") (pin "2") (pinfunction "2_2") (pintype "passive"))
      (node (ref "C148") (pin "2") (pinfunction "2_2") (pintype "passive"))
      (node (ref "IC13") (pin "36") (pinfunction "AVDD_36") (pintype "power_in"))
      (node (ref "IC13") (pin "42") (pinfunction "AVDD_42") (pintype "power_in"))
      (node (ref "L20") (pin "1") (pinfunction "1_1") (pintype "passive"))
      (node (ref "R93") (pin "2") (pinfunction "2_2") (pintype "passive"))
    )
    (net (code "22") (name "/P1V8_DVDD") (class "Default")
      (node (ref "C151") (pin "2") (pinfunction "2_2") (pintype "passive"))
      (node (ref "C153") (pin "2") (pinfunction "2_2") (pintype "passive"))
      (node (ref "C154") (pin "2") (pinfunction "2_2") (pintype "passive"))
      (node (ref "C43") (pin "2") (pinfunction "2_2") (pintype "passive"))
      (node (ref "C51") (pin "2") (pinfunction "2_2") (pintype "passive"))
      (node (ref "C52") (pin "2") (pinfunction "2_2") (pintype "passive"))
      (node (ref "C53") (pin "2") (pinfunction "2_2") (pintype "passive"))
      (node (ref "C82") (pin "2") (pinfunction "2_2") (pintype "passive"))
      (node (ref "C83") (pin "2") (pinfunction "2_2") (pintype "passive"))
      (node (ref "C84") (pin "1") (pinfunction "1_1") (pintype "passive"))
      (node (ref "IC13") (pin "3") (pinfunction "DVDD_3") (pintype "power_in"))
      (node (ref "IC13") (pin "5") (pinfunction "DVDD_5") (pintype "power_in"))
      (node (ref "IC13") (pin "7") (pinfunction "DVDD_7") (pintype "power_in"))
      (node (ref "IC2") (pin "17") (pinfunction "DVDD_(1.8V)_17") (pintype "power_in"))
      (node (ref "IC2") (pin "23") (pinfunction "DVDD_(1.8V)_23") (pintype "power_in"))
      (node (ref "IC2") (pin "30") (pinfunction "DVDD_(1.8V)_30") (pintype "power_in"))
      (node (ref "IC2") (pin "47") (pinfunction "DVDD_(1.8V)_47") (pintype "power_in"))
      (node (ref "IC2") (pin "57") (pinfunction "DVDD_(1.8V)_57") (pintype "power_in"))
      (node (ref "IC2") (pin "64") (pinfunction "DVDD_(1.8V)_64") (pintype "power_in"))
      (node (ref "L22") (pin "1") (pinfunction "1_1") (pintype "passive"))
    )
    (net (code "23") (name "/P2") (class "Default")
      (node (ref "IC2") (pin "52") (pinfunction "PROFILE2_52") (pintype "input"))
    )
    (net (code "24") (name "/P3V3_DAC") (class "Default")
      (node (ref "C124") (pin "2") (pinfunction "2_2") (pintype "passive"))
      (node (ref "C125") (pin "2") (pinfunction "2_2") (pintype "passive"))
      (node (ref "C126") (pin "2") (pinfunction "2_2") (pintype "passive"))
      (node (ref "C129") (pin "2") (pinfunction "2_2") (pintype "passive"))
      (node (ref "C130") (pin "2") (pinfunction "2_2") (pintype "passive"))
      (node (ref "C157") (pin "2") (pinfunction "2_2") (pintype "passive"))
      (node (ref "C158") (pin "2") (pinfunction "2_2") (pintype "passive"))
      (node (ref "C159") (pin "2") (pinfunction "2_2") (pintype "passive"))
      (node (ref "C162") (pin "1") (pinfunction "1_1") (pintype "passive"))
      (node (ref "IC13") (pin "46") (pinfunction "AVDD3_46") (pintype "power_in"))
      (node (ref "IC13") (pin "47") (pinfunction "AVDD3_47") (pintype "power_in"))
      (node (ref "IC13") (pin "49") (pinfunction "AVDD3_49") (pintype "power_in"))
      (node (ref "IC2") (pin "74") (pinfunction "AVDD_(3.3V)_74") (pintype "power_in"))
      (node (ref "IC2") (pin "75") (pinfunction "AVDD_(3.3V)_75") (pintype "power_in"))
      (node (ref "IC2") (pin "76") (pinfunction "AVDD_(3.3V)_76") (pintype "power_in"))
      (node (ref "IC2") (pin "77") (pinfunction "AVDD_(3.3V)_77") (pintype "power_in"))
      (node (ref "IC2") (pin "83") (pinfunction "AVDD_(3.3V)_83") (pintype "power_in"))
      (node (ref "L15") (pin "1") (pinfunction "1_1") (pintype "passive"))
      (node (ref "R96") (pin "2") (pinfunction "2_2") (pintype "passive"))
      (node (ref "R97") (pin "2") (pinfunction "2_2") (pintype "passive"))
      (node (ref "R98") (pin "2") (pinfunction "2_2") (pintype "passive"))
      (node (ref "R99") (pin "2") (pinfunction "2_2") (pintype "passive"))
    )
    (net (code "25") (name "/P3V3_DRV") (class "Default")
      (node (ref "C105") (pin "2") (pinfunction "2_2") (pintype "passive"))
      (node (ref "C106") (pin "2") (pinfunction "2_2") (pintype "passive"))
      (node (ref "C108") (pin "2") (pinfunction "2_2") (pintype "passive"))
      (node (ref "C109") (pin "2") (pinfunction "2_2") (pintype "passive"))
      (node (ref "C110") (pin "2") (pinfunction "2_2") (pintype "passive"))
      (node (ref "C111") (pin "2") (pinfunction "2_2") (pintype "passive"))
      (node (ref "C114") (pin "1") (pinfunction "1_1") (pintype "passive"))
      (node (ref "C137") (pin "2") (pinfunction "2_2") (pintype "passive"))
      (node (ref "C141") (pin "2") (pinfunction "2_2") (pintype "passive"))
      (node (ref "C142") (pin "2") (pinfunction "2_2") (pintype "passive"))
      (node (ref "C85") (pin "2") (pinfunction "2_2") (pintype "passive"))
      (node (ref "IC13") (pin "1") (pinfunction "DVDD_I/O_1") (pintype "power_in"))
      (node (ref "IC13") (pin "14") (pinfunction "AVDD3_14") (pintype "power_in"))
      (node (ref "IC13") (pin "37") (pinfunction "AVDD3_37") (pintype "power_in"))
      (node (ref "IC2") (pin "11") (pinfunction "DVDD_I/O_(3.3V)_11") (pintype "power_in"))
      (node (ref "IC2") (pin "15") (pinfunction "DVDD_I/O_(3.3V)_15") (pintype "power_in"))
      (node (ref "IC2") (pin "21") (pinfunction "DVDD_I/O_(3.3V)_21") (pintype "power_in"))
      (node (ref "IC2") (pin "28") (pinfunction "DVDD_I/O_(3.3V)_28") (pintype "power_in"))
      (node (ref "IC2") (pin "45") (pinfunction "DVDD_I/O_(3.3V)_45") (pintype "power_in"))
      (node (ref "IC2") (pin "56") (pinfunction "DVDD_I/O_(3.3V)_56") (pintype "power_in"))
      (node (ref "IC2") (pin "66") (pinfunction "DVDD_I/O_(3.3V)_66") (pintype "power_in"))
      (node (ref "L18") (pin "1") (pinfunction "1_1") (pintype "passive"))
    )
    (net (code "26") (name "/PLL_LOCK") (class "Default")
      (node (ref "IC2") (pin "19") (pinfunction "PLL_LOCK_19") (pintype "output"))
    )
    (net (code "27") (name "/RESET") (class "Default")
      (node (ref "IC13") (pin "59") (pinfunction "RESET_59") (pintype "input"))
      (node (ref "IC2") (pin "14") (pinfunction "MASTER_RESET_14") (pintype "input"))
    )
    (net (code "28") (name "/RSET") (class "Default")
      (node (ref "IC13") (pin "48") (pinfunction "DAC_RSET_48") (pintype "output"))
      (node (ref "R15") (pin "1") (pinfunction "1_1") (pintype "passive"))
    )
    (net (code "29") (name "/RSET1") (class "Default")
      (node (ref "IC2") (pin "84") (pinfunction "DAC_RSET_84") (pintype "output"))
      (node (ref "R112") (pin "1") (pinfunction "1_1") (pintype "passive"))
    )
    (net (code "30") (name "/S1") (class "Default")
      (node (ref "IC13") (pin "9") (pinfunction "S1_9") (pintype "bidirectional"))
      (node (ref "R104") (pin "2") (pinfunction "2_2") (pintype "passive"))
      (node (ref "R96") (pin "1") (pinfunction "1_1") (pintype "passive"))
    )
    (net (code "31") (name "/S2") (class "Default")
      (node (ref "IC13") (pin "10") (pinfunction "S2_10") (pintype "bidirectional"))
      (node (ref "R105") (pin "2") (pinfunction "2_2") (pintype "passive"))
      (node (ref "R97") (pin "1") (pinfunction "1_1") (pintype "passive"))
    )
    (net (code "32") (name "/S3") (class "Default")
      (node (ref "IC13") (pin "54") (pinfunction "S3_54") (pintype "bidirectional"))
      (node (ref "R106") (pin "2") (pinfunction "2_2") (pintype "passive"))
      (node (ref "R98") (pin "1") (pinfunction "1_1") (pintype "passive"))
    )
    (net (code "33") (name "/S4") (class "Default")
      (node (ref "IC13") (pin "55") (pinfunction "S4_55") (pintype "bidirectional"))
      (node (ref "R107") (pin "2") (pinfunction "2_2") (pintype "passive"))
      (node (ref "R99") (pin "1") (pinfunction "1_1") (pintype "passive"))
    )
    (net (code "34") (name "/SCKI") (class "Default")
      (node (ref "IC13") (pin "64") (pinfunction "SCLK_64") (pintype "input"))
      (node (ref "IC2") (pin "69") (pinfunction "SCLK_69") (pintype "input"))
      (node (ref "R40") (pin "2") (pinfunction "2_2") (pintype "passive"))
    )
    (net (code "35") (name "/SDI") (class "Default")
      (node (ref "IC13") (pin "63") (pinfunction "SDIO_63") (pintype "bidirectional"))
      (node (ref "IC2") (pin "67") (pinfunction "SDIO_67") (pintype "bidirectional"))
      (node (ref "R41") (pin "2") (pinfunction "2_2") (pintype "passive"))
    )
    (net (code "36") (name "/SDO") (class "Default")
      (node (ref "IC13") (pin "62") (pinfunction "SDO_62") (pintype "output"))
      (node (ref "IC2") (pin "68") (pinfunction "SDO_68") (pintype "output"))
    )
    (net (code "37") (name "/SYNC_CLK") (class "Default")
      (node (ref "IC2") (pin "55") (pinfunction "SYNC_CLK_55") (pintype "output"))
    )
    (net (code "38") (name "/SYNC_IN_N") (class "Default")
      (node (ref "IC2") (pin "8") (pinfunction "SYNC_IN-_8") (pintype "input"))
    )
    (net (code "39") (name "/SYNC_IN_P") (class "Default")
      (node (ref "IC2") (pin "7") (pinfunction "SYNC_IN+_7") (pintype "input"))
    )
    (net (code "40") (name "/SYNC_OUT_N") (class "Default")
      (node (ref "IC2") (pin "10") (pinfunction "SYNC_OUT-_10") (pintype "output"))
    )
    (net (code "41") (name "/SYNC_OUT_P") (class "Default")
      (node (ref "IC2") (pin "9") (pinfunction "SYNC_OUT+_9") (pintype "output"))
    )
    (net (code "42") (name "/SYNC_SMP_ERR") (class "Default")
      (node (ref "IC2") (pin "12") (pinfunction "SYNC_SMP_ERR_12") (pintype "output"))
    )
    (net (code "44") (name "GND") (class "Default")
      (node (ref "C105") (pin "1") (pinfunction "1_1") (pintype "passive"))
      (node (ref "C106") (pin "1") (pinfunction "1_1") (pintype "passive"))
      (node (ref "C108") (pin "1") (pinfunction "1_1") (pintype "passive"))
      (node (ref "C109") (pin "1") (pinfunction "1_1") (pintype "passive"))
      (node (ref "C110") (pin "1") (pinfunction "1_1") (pintype "passive"))
      (node (ref "C111") (pin "1") (pinfunction "1_1") (pintype "passive"))
      (node (ref "C114") (pin "2") (pinfunction "2_2") (pintype "passive"))
      (node (ref "C115") (pin "2") (pinfunction "2_2") (pintype "passive"))
      (node (ref "C116") (pin "1") (pinfunction "1_1") (pintype "passive"))
      (node (ref "C117") (pin "1") (pinfunction "1_1") (pintype "passive"))
      (node (ref "C118") (pin "1") (pinfunction "1_1") (pintype "passive"))
      (node (ref "C119") (pin "1") (pinfunction "1_1") (pintype "passive"))
      (node (ref "C120") (pin "1") (pinfunction "1_1") (pintype "passive"))
      (node (ref "C124") (pin "1") (pinfunction "1_1") (pintype "passive"))
      (node (ref "C125") (pin "1") (pinfunction "1_1") (pintype "passive"))
      (node (ref "C126") (pin "1") (pinfunction "1_1") (pintype "passive"))
      (node (ref "C127") (pin "1") (pinfunction "1_1") (pintype "passive"))
      (node (ref "C128") (pin "1") (pinfunction "1_1") (pintype "passive"))
      (node (ref "C129") (pin "1") (pinfunction "1_1") (pintype "passive"))
      (node (ref "C130") (pin "1") (pinfunction "1_1") (pintype "passive"))
      (node (ref "C133") (pin "1") (pinfunction "1_1") (pintype "passive"))
      (node (ref "C134") (pin "1") (pinfunction "1_1") (pintype "passive"))
      (node (ref "C135") (pin "1") (pinfunction "1_1") (pintype "passive"))
      (node (ref "C136") (pin "1") (pinfunction "1_1") (pintype "passive"))
      (node (ref "C137") (pin "1") (pinfunction "1_1") (pintype "passive"))
      (node (ref "C138") (pin "1") (pinfunction "1_1") (pintype "passive"))
      (node (ref "C140") (pin "1") (pinfunction "1_1") (pintype "passive"))
      (node (ref "C141") (pin "1") (pinfunction "1_1") (pintype "passive"))
      (node (ref "C142") (pin "1") (pinfunction "1_1") (pintype "passive"))
      (node (ref "C143") (pin "1") (pinfunction "1_1") (pintype "passive"))
      (node (ref "C144") (pin "1") (pinfunction "1_1") (pintype "passive"))
      (node (ref "C146") (pin "1") (pinfunction "1_1") (pintype "passive"))
      (node (ref "C147") (pin "1") (pinfunction "1_1") (pintype "passive"))
      (node (ref "C148") (pin "1") (pinfunction "1_1") (pintype "passive"))
      (node (ref "C149") (pin "1") (pinfunction "1_1") (pintype "passive"))
      (node (ref "C150") (pin "1") (pinfunction "1_1") (pintype "passive"))
      (node (ref "C151") (pin "1") (pinfunction "1_1") (pintype "passive"))
      (node (ref "C153") (pin "1") (pinfunction "1_1") (pintype "passive"))
      (node (ref "C154") (pin "1") (pinfunction "1_1") (pintype "passive"))
      (node (ref "C157") (pin "1") (pinfunction "1_1") (pintype "passive"))
      (node (ref "C158") (pin "1") (pinfunction "1_1") (pintype "passive"))
      (node (ref "C159") (pin "1") (pinfunction "1_1") (pintype "passive"))
      (node (ref "C162") (pin "2") (pinfunction "2_2") (pintype "passive"))
      (node (ref "C26") (pin "1") (pinfunction "1_1") (pintype "passive"))
      (node (ref "C43") (pin "1") (pinfunction "1_1") (pintype "passive"))
      (node (ref "C51") (pin "1") (pinfunction "1_1") (pintype "passive"))
      (node (ref "C52") (pin "1") (pinfunction "1_1") (pintype "passive"))
      (node (ref "C53") (pin "1") (pinfunction "1_1") (pintype "passive"))
      (node (ref "C82") (pin "1") (pinfunction "1_1") (pintype "passive"))
      (node (ref "C83") (pin "1") (pinfunction "1_1") (pintype "passive"))
      (node (ref "C84") (pin "2") (pinfunction "2_2") (pintype "passive"))
      (node (ref "C85") (pin "1") (pinfunction "1_1") (pintype "passive"))
      (node (ref "C87") (pin "1") (pinfunction "1_1") (pintype "passive"))
      (node (ref "IC13") (pin "2") (pinfunction "DVSS_2") (pintype "power_in"))
      (node (ref "IC13") (pin "33") (pinfunction "AVSS_33") (pintype "power_in"))
      (node (ref "IC13") (pin "39") (pinfunction "AVSS_39") (pintype "power_in"))
      (node (ref "IC13") (pin "4") (pinfunction "DVSS_4") (pintype "power_in"))
      (node (ref "IC13") (pin "43") (pinfunction "AVSS_43") (pintype "power_in"))
      (node (ref "IC13") (pin "52") (pinfunction "AVSS_52") (pintype "power_in"))
      (node (ref "IC13") (pin "56") (pinfunction "DVSS_56") (pintype "power_in"))
      (node (ref "IC13") (pin "57") (pinfunction "DVSS_57") (pintype "power_in"))
      (node (ref "IC13") (pin "58") (pinfunction "PWRDOWN_58") (pintype "input"))
      (node (ref "IC13") (pin "6") (pinfunction "DVSS_6") (pintype "power_in"))
      (node (ref "IC13") (pin "65") (pinfunction "EP_65") (pintype "power_in"))
      (node (ref "IC13") (pin "8") (pinfunction "DVSS_8") (pintype "power_in"))
      (node (ref "IC2") (pin "101") (pinfunction "EP(GND)_101") (pintype "power_in"))
      (node (ref "IC2") (pin "13") (pinfunction "DGND_13") (pintype "power_in"))
      (node (ref "IC2") (pin "16") (pinfunction "DGND_16") (pintype "power_in"))
      (node (ref "IC2") (pin "18") (pinfunction "EXT_PWR_DWN_18") (pintype "input"))
      (node (ref "IC2") (pin "22") (pinfunction "DGND_22") (pintype "power_in"))
      (node (ref "IC2") (pin "25") (pinfunction "D15_25") (pintype "input"))
      (node (ref "IC2") (pin "26") (pinfunction "D14_26") (pintype "input"))
      (node (ref "IC2") (pin "27") (pinfunction "D13_27") (pintype "input"))
      (node (ref "IC2") (pin "29") (pinfunction "DGND_29") (pintype "power_in"))
      (node (ref "IC2") (pin "31") (pinfunction "D12_31") (pintype "input"))
      (node (ref "IC2") (pin "32") (pinfunction "D11_32") (pintype "input"))
      (node (ref "IC2") (pin "33") (pinfunction "D10_33") (pintype "input"))
      (node (ref "IC2") (pin "34") (pinfunction "D9_34") (pintype "input"))
      (node (ref "IC2") (pin "35") (pinfunction "D8_35") (pintype "input"))
      (node (ref "IC2") (pin "36") (pinfunction "D7_36") (pintype "input"))
      (node (ref "IC2") (pin "37") (pinfunction "D6_37") (pintype "input"))
      (node (ref "IC2") (pin "38") (pinfunction "D5_38") (pintype "input"))
      (node (ref "IC2") (pin "39") (pinfunction "D4_39") (pintype "input"))
      (node (ref "IC2") (pin "4") (pinfunction "AGND_4") (pintype "power_in"))
      (node (ref "IC2") (pin "41") (pinfunction "TxENABLE_41") (pintype "input"))
      (node (ref "IC2") (pin "42") (pinfunction "D3_42") (pintype "input"))
      (node (ref "IC2") (pin "43") (pinfunction "D2_43") (pintype "input"))
      (node (ref "IC2") (pin "44") (pinfunction "D1_44") (pintype "input"))
      (node (ref "IC2") (pin "46") (pinfunction "DGND_46") (pintype "power_in"))
      (node (ref "IC2") (pin "48") (pinfunction "D0_48") (pintype "input"))
      (node (ref "IC2") (pin "49") (pinfunction "F1_49") (pintype "input"))
      (node (ref "IC2") (pin "5") (pinfunction "AGND_5") (pintype "power_in"))
      (node (ref "IC2") (pin "50") (pinfunction "F0_50") (pintype "input"))
      (node (ref "IC2") (pin "51") (pinfunction "DGND_51") (pintype "power_in"))
      (node (ref "IC2") (pin "58") (pinfunction "DGND_58") (pintype "power_in"))
      (node (ref "IC2") (pin "62") (pinfunction "DRCTL_62") (pintype "input"))
      (node (ref "IC2") (pin "63") (pinfunction "DRHOLD_63") (pintype "input"))
      (node (ref "IC2") (pin "65") (pinfunction "DGND_65") (pintype "power_in"))
      (node (ref "IC2") (pin "73") (pinfunction "AGND_73") (pintype "power_in"))
      (node (ref "IC2") (pin "78") (pinfunction "AGND_78") (pintype "power_in"))
      (node (ref "IC2") (pin "79") (pinfunction "AGND_79") (pintype "power_in"))
      (node (ref "IC2") (pin "82") (pinfunction "AGND_82") (pintype "power_in"))
      (node (ref "IC2") (pin "85") (pinfunction "AGND_85") (pintype "power_in"))
      (node (ref "IC2") (pin "88") (pinfunction "AGND_88") (pintype "power_in"))
      (node (ref "IC2") (pin "96") (pinfunction "AGND_96") (pintype "power_in"))
      (node (ref "R100") (pin "2") (pinfunction "2_2") (pintype "passive"))
      (node (ref "R104") (pin "1") (pinfunction "1_1") (pintype "passive"))
      (node (ref "R105") (pin "1") (pinfunction "1_1") (pintype "passive"))
      (node (ref "R106") (pin "1") (pinfunction "1_1") (pintype "passive"))
      (node (ref "R107") (pin "1") (pinfunction "1_1") (pintype "passive"))
      (node (ref "R112") (pin "2") (pinfunction "2_2") (pintype "passive"))
      (node (ref "R15") (pin "2") (pinfunction "2_2") (pintype "passive"))
      (node (ref "R88") (pin "1") (pinfunction "1_1") (pintype "passive"))
      (node (ref "R89") (pin "2") (pinfunction "2_2") (pintype "passive"))
      (node (ref "R94") (pin "1") (pinfunction "1_1") (pintype "passive"))
    )
    (net (code "45") (name "Net-(C26-Pad2)") (class "Default")
      (node (ref "C26") (pin "2") (pinfunction "2_2") (pintype "passive"))
      (node (ref "R41") (pin "1") (pinfunction "1_1") (pintype "passive"))
    )
    (net (code "46") (name "Net-(C72-Pad2)") (class "Default")
      (node (ref "C72") (pin "2") (pinfunction "2_2") (pintype "passive"))
      (node (ref "C99") (pin "2") (pinfunction "2_2") (pintype "passive"))
      (node (ref "R92") (pin "1") (pinfunction "1_1") (pintype "passive"))
    )
    (net (code "47") (name "Net-(C87-Pad2)") (class "Default")
      (node (ref "C87") (pin "2") (pinfunction "2_2") (pintype "passive"))
      (node (ref "R40") (pin "1") (pinfunction "1_1") (pintype "passive"))
    )
    (net (code "48") (name "Net-(C107-Pad2)") (class "Default")
      (node (ref "C107") (pin "2") (pinfunction "2_2") (pintype "passive"))
      (node (ref "C44") (pin "2") (pinfunction "2_2") (pintype "passive"))
      (node (ref "R113") (pin "1") (pinfunction "1_1") (pintype "passive"))
    )
    (net (code "49") (name "Net-(IC2-IOUT-Pad80)") (class "Default")
      (node (ref "IC2") (pin "80") (pinfunction "IOUT_80") (pintype "output"))
      (node (ref "R56") (pin "1") (pinfunction "1_1") (pintype "passive"))
    )
    (net (code "50") (name "Net-(IC2-IOUT-Pad81)") (class "Default")
      (node (ref "IC2") (pin "81") (pinfunction "IOUT_81") (pintype "output"))
      (node (ref "R78") (pin "1") (pinfunction "1_1") (pintype "passive"))
    )
    (net (code "51") (name "Net-(IC2-OSK)") (class "Default")
      (node (ref "IC2") (pin "60") (pinfunction "OSK_60") (pintype "input"))
      (node (ref "R100") (pin "1") (pinfunction "1_1") (pintype "passive"))
    )
    (net (code "52") (name "Net-(IC2-XTAL_SEL)") (class "Default")
      (node (ref "IC2") (pin "95") (pinfunction "XTAL_SEL_95") (pintype "input"))
      (node (ref "R88") (pin "2") (pinfunction "2_2") (pintype "passive"))
    )
    (net (code "53") (name "Net-(IC13-CLKMODESEL)") (class "Default")
      (node (ref "IC13") (pin "32") (pinfunction "CLKMODESEL_32") (pintype "input"))
      (node (ref "R93") (pin "1") (pinfunction "1_1") (pintype "passive"))
      (node (ref "R94") (pin "2") (pinfunction "2_2") (pintype "passive"))
    )
    (net (code "54") (name "Net-(R90-Pad1)") (class "Default")
      (node (ref "R90") (pin "1") (pinfunction "1_1") (pintype "passive"))
      (node (ref "R92") (pin "2") (pinfunction "2_2") (pintype "passive"))
    )
    (net (code "55") (name "Net-(R113-Pad2)") (class "Default")
      (node (ref "R113") (pin "2") (pinfunction "2_2") (pintype "passive"))
      (node (ref "R140") (pin "1") (pinfunction "1_1") (pintype "passive"))
    )
    (net (code "56") (name "P1V8A") (class "Default")
      (node (ref "L16") (pin "2") (pinfunction "2_2") (pintype "passive"))
      (node (ref "L17") (pin "2") (pinfunction "2_2") (pintype "passive"))
      (node (ref "L19") (pin "2") (pinfunction "2_2") (pintype "passive"))
      (node (ref "L20") (pin "2") (pinfunction "2_2") (pintype "passive"))
      (node (ref "L21") (pin "2") (pinfunction "2_2") (pintype "passive"))
      (node (ref "L22") (pin "2") (pinfunction "2_2") (pintype "passive"))
    )
    (net (code "57") (name "P3V3A") (class "Default")
      (node (ref "L15") (pin "2") (pinfunction "2_2") (pintype "passive"))
      (node (ref "L18") (pin "2") (pinfunction "2_2") (pintype "passive"))
    )
    (net (code "58") (name "unconnected-(IC2-DROVER-Pad61)") (class "Default")
      (node (ref "IC2") (pin "61") (pinfunction "DROVER_61") (pintype "output+no_connect"))
    )
    (net (code "59") (name "unconnected-(IC2-NC-Pad1)") (class "Default")
      (node (ref "IC2") (pin "1") (pinfunction "NC_1") (pintype "passive+no_connect"))
    )
    (net (code "60") (name "unconnected-(IC2-NC-Pad20)") (class "Default")
      (node (ref "IC2") (pin "20") (pinfunction "NC_20") (pintype "passive+no_connect"))
    )
    (net (code "61") (name "unconnected-(IC2-NC-Pad72)") (class "Default")
      (node (ref "IC2") (pin "72") (pinfunction "NC_72") (pintype "passive+no_connect"))
    )
    (net (code "62") (name "unconnected-(IC2-NC-Pad86)") (class "Default")
      (node (ref "IC2") (pin "86") (pinfunction "NC_86") (pintype "passive+no_connect"))
    )
    (net (code "63") (name "unconnected-(IC2-NC-Pad87)") (class "Default")
      (node (ref "IC2") (pin "87") (pinfunction "NC_87") (pintype "passive+no_connect"))
    )
    (net (code "64") (name "unconnected-(IC2-NC-Pad93)") (class "Default")
      (node (ref "IC2") (pin "93") (pinfunction "NC_93") (pintype "passive+no_connect"))
    )
    (net (code "65") (name "unconnected-(IC2-NC-Pad97)") (class "Default")
      (node (ref "IC2") (pin "97") (pinfunction "NC_97") (pintype "passive+no_connect"))
    )
    (net (code "66") (name "unconnected-(IC2-NC-Pad98)") (class "Default")
      (node (ref "IC2") (pin "98") (pinfunction "NC_98") (pintype "passive+no_connect"))
    )
    (net (code "67") (name "unconnected-(IC2-NC-Pad99)") (class "Default")
      (node (ref "IC2") (pin "99") (pinfunction "NC_99") (pintype "passive+no_connect"))
    )
    (net (code "68") (name "unconnected-(IC2-NC-Pad100)") (class "Default")
      (node (ref "IC2") (pin "100") (pinfunction "NC_100") (pintype "passive+no_connect"))
    )
    (net (code "69") (name "unconnected-(IC2-PDCLK-Pad40)") (class "Default")
      (node (ref "IC2") (pin "40") (pinfunction "PDCLK_40") (pintype "output+no_connect"))
    )
    (net (code "70") (name "unconnected-(IC2-RAM_SWP_OVR-Pad24)") (class "Default")
      (node (ref "IC2") (pin "24") (pinfunction "RAM_SWP_OVR_24") (pintype "output+no_connect"))
    )
    (net (code "71") (name "unconnected-(IC2-REFCLK_OUT-Pad94)") (class "Default")
      (node (ref "IC2") (pin "94") (pinfunction "REFCLK_OUT_94") (pintype "output"))
    )
    (net (code "72") (name "unconnected-(IC13-FDBK_IN-Pad41)") (class "Default")
      (node (ref "IC13") (pin "41") (pinfunction "FDBK_IN_41") (pintype "input+no_connect"))
    )
    (net (code "73") (name "unconnected-(IC13-FDBK_INB-Pad40)") (class "Default")
      (node (ref "IC13") (pin "40") (pinfunction "FDBK_INB_40") (pintype "input+no_connect"))
    )
    (net (code "74") (name "unconnected-(IC13-NC-Pad12)") (class "Default")
      (node (ref "IC13") (pin "12") (pinfunction "NC_12") (pintype "passive+no_connect"))
    )
    (net (code "75") (name "unconnected-(IC13-NC-Pad13)") (class "Default")
      (node (ref "IC13") (pin "13") (pinfunction "NC_13") (pintype "passive+no_connect"))
    )
    (net (code "76") (name "unconnected-(IC13-NC-Pad15)") (class "Default")
      (node (ref "IC13") (pin "15") (pinfunction "NC_15") (pintype "passive+no_connect"))
    )
    (net (code "77") (name "unconnected-(IC13-NC-Pad16)") (class "Default")
      (node (ref "IC13") (pin "16") (pinfunction "NC_16") (pintype "passive+no_connect"))
    )
    (net (code "78") (name "unconnected-(IC13-NC-Pad17)") (class "Default")
      (node (ref "IC13") (pin "17") (pinfunction "NC_17") (pintype "passive+no_connect"))
    )
    (net (code "79") (name "unconnected-(IC13-NC-Pad18)") (class "Default")
      (node (ref "IC13") (pin "18") (pinfunction "NC_18") (pintype "passive+no_connect"))
    )
    (net (code "80") (name "unconnected-(IC13-NC-Pad20)") (class "Default")
      (node (ref "IC13") (pin "20") (pinfunction "NC_20") (pintype "passive+no_connect"))
    )
    (net (code "81") (name "unconnected-(IC13-NC-Pad21)") (class "Default")
      (node (ref "IC13") (pin "21") (pinfunction "NC_21") (pintype "passive+no_connect"))
    )
    (net (code "82") (name "unconnected-(IC13-NC-Pad22)") (class "Default")
      (node (ref "IC13") (pin "22") (pinfunction "NC_22") (pintype "passive+no_connect"))
    )
    (net (code "83") (name "unconnected-(IC13-OUT-Pad35)") (class "Default")
      (node (ref "IC13") (pin "35") (pinfunction "OUT_35") (pintype "output+no_connect"))
    )
    (net (code "84") (name "unconnected-(IC13-OUTB-Pad34)") (class "Default")
      (node (ref "IC13") (pin "34") (pinfunction "OUTB_34") (pintype "output+no_connect"))
    )
    (net (code "85") (name "unconnected-(IC13-OUT_CMOS-Pad38)") (class "Default")
      (node (ref "IC13") (pin "38") (pinfunction "OUT_CMOS_38") (pintype "output+no_connect"))
    )
  )
)
